# CAN_Tranceiver.net
KiCad netlist of a schematic drawn in Altium Designer
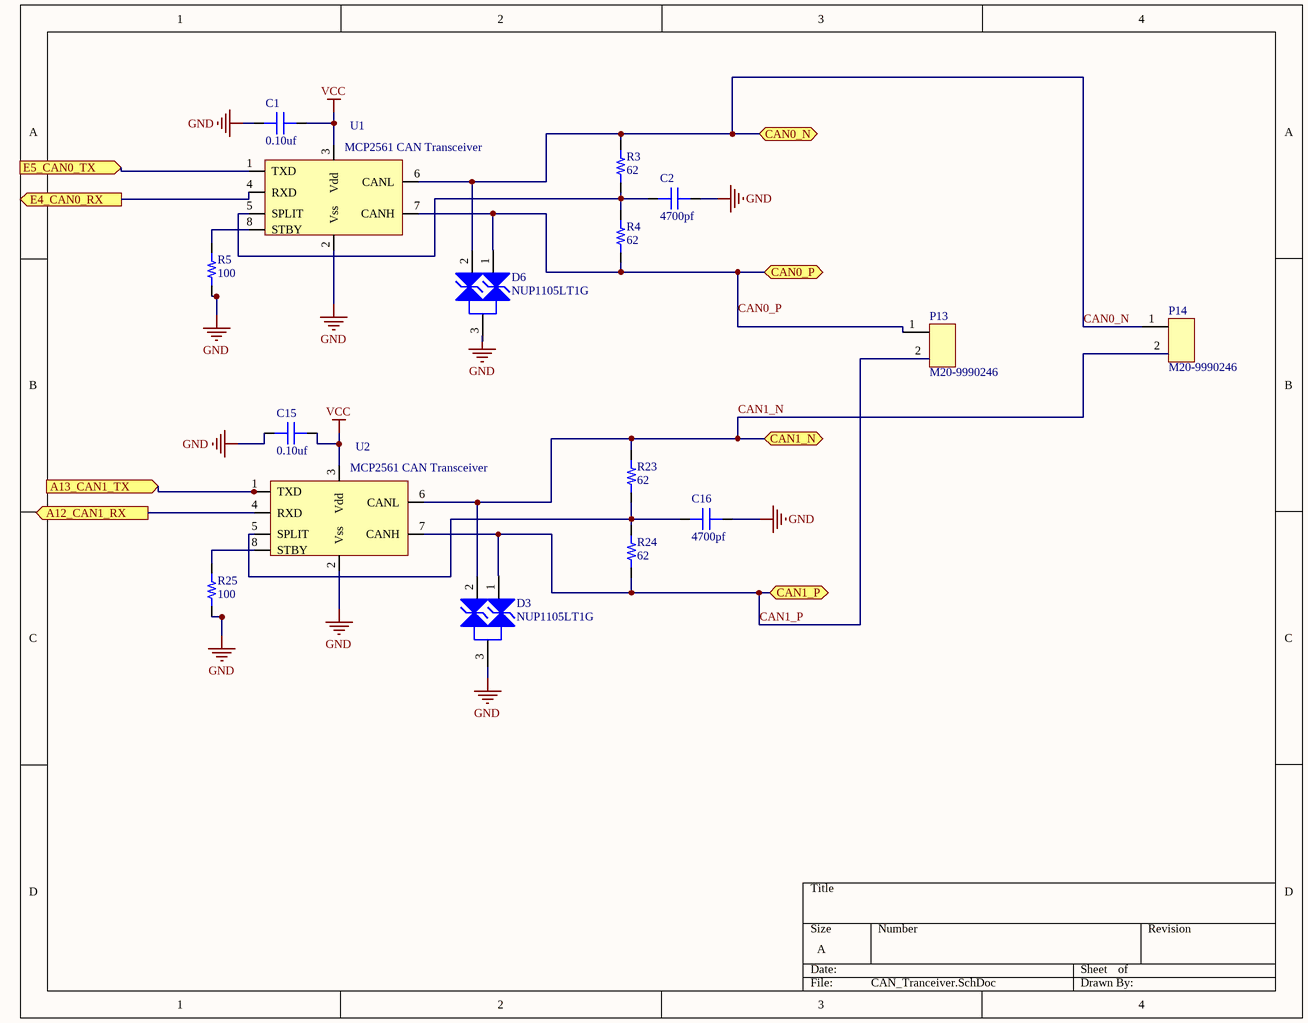
[diagram p0: CAN_Tranceiver.SchDoc]

(export (version "E")
  (design (tool "Eeschema 10.0.6"))
  (components
    (comp (ref "C1")
      (value "0.10uf")
      (footprint "CAP 0603/1608")
      (fields
        (field (name "Comment") "Capacitor MLCC 0.10uf 50V CAP 0603/1608")
        (field (name "CREATED_BY") "Nick Mah")
      )
      (libsource (lib "Altium-Lib") (part "Capacitor"))
    )
    (comp (ref "C2")
      (value "4700pf")
      (footprint "CAP 0603/1608")
      (fields
        (field (name "Comment") "Capacitor MLCC 4700pf 50V CAP 0603/1608")
        (field (name "CREATED_BY") "Nick Mah")
      )
      (libsource (lib "Altium-Lib") (part "Capacitor"))
    )
    (comp (ref "C15")
      (value "0.10uf")
      (footprint "CAP 0603/1608")
      (fields
        (field (name "Comment") "Capacitor MLCC 0.10uf 50V CAP 0603/1608")
        (field (name "CREATED_BY") "Nick Mah")
      )
      (libsource (lib "Altium-Lib") (part "Capacitor"))
    )
    (comp (ref "C16")
      (value "4700pf")
      (footprint "CAP 0603/1608")
      (fields
        (field (name "Comment") "Capacitor MLCC 4700pf 50V CAP 0603/1608")
        (field (name "CREATED_BY") "Nick Mah")
      )
      (libsource (lib "Altium-Lib") (part "Capacitor"))
    )
    (comp (ref "D3")
      (value "NUP1105LT1G")
      (footprint "SOT-23 (TO-236)")
      (description "ESD Protection Diode")
      (fields (field (name "POWER") "350W"))
      (libsource (lib "Altium-Lib") (part "NUP1105LT1G"))
    )
    (comp (ref "D6")
      (value "NUP1105LT1G")
      (footprint "SOT-23 (TO-236)")
      (description "ESD Protection Diode")
      (fields (field (name "POWER") "350W"))
      (libsource (lib "Altium-Lib") (part "NUP1105LT1G"))
    )
    (comp (ref "P13")
      (value "M20-9990246")
      (footprint "M20-9990246")
      (description "2 Pin VCC Power Header, Male")
      (fields (field (name "CREATED_BY") "Austin") (field (name "UPDATED_BY") "Null"))
      (libsource (lib "Altium-Lib") (part "M20-9990246"))
    )
    (comp (ref "P14")
      (value "M20-9990246")
      (footprint "M20-9990246")
      (description "2 Pin VCC Power Header, Male")
      (fields (field (name "CREATED_BY") "Austin") (field (name "UPDATED_BY") "Null"))
      (libsource (lib "Altium-Lib") (part "M20-9990246"))
    )
    (comp (ref "R3")
      (value "62")
      (footprint "RES 0603/1608")
      (fields
        (field (name "TOLERANCE") "5%")
        (field (name "POWER") "1/10W")
        (field (name "Comment") "Resistor 62 0603 1/10W 5%")
        (field (name "CREATED_BY") "Nick Mah")
      )
      (libsource (lib "Altium-Lib") (part "Resistor"))
    )
    (comp (ref "R4")
      (value "62")
      (footprint "RES 0603/1608")
      (fields
        (field (name "TOLERANCE") "5%")
        (field (name "POWER") "1/10W")
        (field (name "Comment") "Resistor 62 0603 1/10W 5%")
        (field (name "CREATED_BY") "Nick Mah")
      )
      (libsource (lib "Altium-Lib") (part "Resistor"))
    )
    (comp (ref "R5")
      (value "100")
      (footprint "RES 0603/1608")
      (fields
        (field (name "TOLERANCE") "10%")
        (field (name "POWER") "1/10W")
        (field (name "Comment") "Resistor 100 0603 1/10W 10%")
        (field (name "CREATED_BY") "Nick Mah")
      )
      (libsource (lib "Altium-Lib") (part "Resistor"))
    )
    (comp (ref "R23")
      (value "62")
      (footprint "RES 0603/1608")
      (fields
        (field (name "TOLERANCE") "5%")
        (field (name "POWER") "1/10W")
        (field (name "Comment") "Resistor 62 0603 1/10W 5%")
        (field (name "CREATED_BY") "Nick Mah")
      )
      (libsource (lib "Altium-Lib") (part "Resistor"))
    )
    (comp (ref "R24")
      (value "62")
      (footprint "RES 0603/1608")
      (fields
        (field (name "TOLERANCE") "5%")
        (field (name "POWER") "1/10W")
        (field (name "Comment") "Resistor 62 0603 1/10W 5%")
        (field (name "CREATED_BY") "Nick Mah")
      )
      (libsource (lib "Altium-Lib") (part "Resistor"))
    )
    (comp (ref "R25")
      (value "100")
      (footprint "RES 0603/1608")
      (fields
        (field (name "TOLERANCE") "10%")
        (field (name "POWER") "1/10W")
        (field (name "Comment") "Resistor 100 0603 1/10W 10%")
        (field (name "CREATED_BY") "Nick Mah")
      )
      (libsource (lib "Altium-Lib") (part "Resistor"))
    )
    (comp (ref "U1")
      (value "MCP2561 CAN Transceiver")
      (footprint "SOIC-8")
      (fields (field (name "MFRPARTNO") "MCP2561") (field (name "CREATED_BY") "Angel Delgado"))
      (libsource (lib "Altium-Lib") (part "MCP2561 CAN Transceiver"))
    )
    (comp (ref "U2")
      (value "MCP2561 CAN Transceiver")
      (footprint "SOIC-8")
      (fields (field (name "MFRPARTNO") "MCP2561") (field (name "CREATED_BY") "Angel Delgado"))
      (libsource (lib "Altium-Lib") (part "MCP2561 CAN Transceiver"))
    )
  )
  (nets
    (net (code "1") (name "/A12_CAN1_RX") (class "Default")
      (node (ref "U2") (pin "4") (pinfunction "RXD_4") (pintype "passive"))
    )
    (net (code "2") (name "/A13_CAN1_TX") (class "Default")
      (node (ref "U2") (pin "1") (pinfunction "TXD_1") (pintype "passive"))
    )
    (net (code "3") (name "/CAN0_N") (class "Default")
      (node (ref "D6") (pin "2") (pinfunction "K_2") (pintype "passive"))
      (node (ref "P14") (pin "1") (pinfunction "1_1") (pintype "passive"))
      (node (ref "R3") (pin "1") (pinfunction "1_1") (pintype "passive"))
      (node (ref "U1") (pin "6") (pinfunction "CANL_6") (pintype "passive"))
    )
    (net (code "4") (name "/CAN0_P") (class "Default")
      (node (ref "D6") (pin "1") (pinfunction "K_1") (pintype "passive"))
      (node (ref "P13") (pin "1") (pinfunction "1_1") (pintype "passive"))
      (node (ref "R4") (pin "2") (pinfunction "2_2") (pintype "passive"))
      (node (ref "U1") (pin "7") (pinfunction "CANH_7") (pintype "passive"))
    )
    (net (code "5") (name "/CAN1_N") (class "Default")
      (node (ref "D3") (pin "2") (pinfunction "K_2") (pintype "passive"))
      (node (ref "P14") (pin "2") (pinfunction "2_2") (pintype "passive"))
      (node (ref "R23") (pin "1") (pinfunction "1_1") (pintype "passive"))
      (node (ref "U2") (pin "6") (pinfunction "CANL_6") (pintype "passive"))
    )
    (net (code "6") (name "/CAN1_P") (class "Default")
      (node (ref "D3") (pin "1") (pinfunction "K_1") (pintype "passive"))
      (node (ref "P13") (pin "2") (pinfunction "2_2") (pintype "passive"))
      (node (ref "R24") (pin "2") (pinfunction "2_2") (pintype "passive"))
      (node (ref "U2") (pin "7") (pinfunction "CANH_7") (pintype "passive"))
    )
    (net (code "7") (name "/E4_CAN0_RX") (class "Default")
      (node (ref "U1") (pin "4") (pinfunction "RXD_4") (pintype "passive"))
    )
    (net (code "8") (name "/E5_CAN0_TX") (class "Default")
      (node (ref "U1") (pin "1") (pinfunction "TXD_1") (pintype "passive"))
    )
    (net (code "9") (name "GND") (class "Default")
      (node (ref "C1") (pin "1") (pinfunction "1_1") (pintype "passive"))
      (node (ref "C15") (pin "1") (pinfunction "1_1") (pintype "passive"))
      (node (ref "C16") (pin "1") (pinfunction "1_1") (pintype "passive"))
      (node (ref "C2") (pin "1") (pinfunction "1_1") (pintype "passive"))
      (node (ref "D3") (pin "3") (pinfunction "K_3") (pintype "passive"))
      (node (ref "D6") (pin "3") (pinfunction "K_3") (pintype "passive"))
      (node (ref "R25") (pin "1") (pinfunction "1_1") (pintype "passive"))
      (node (ref "R5") (pin "1") (pinfunction "1_1") (pintype "passive"))
      (node (ref "U1") (pin "2") (pinfunction "Vss_2") (pintype "passive"))
      (node (ref "U2") (pin "2") (pinfunction "Vss_2") (pintype "passive"))
    )
    (net (code "10") (name "Net-(U1-SPLIT)") (class "Default")
      (node (ref "C2") (pin "2") (pinfunction "2_2") (pintype "passive"))
      (node (ref "R3") (pin "2") (pinfunction "2_2") (pintype "passive"))
      (node (ref "R4") (pin "1") (pinfunction "1_1") (pintype "passive"))
      (node (ref "U1") (pin "5") (pinfunction "SPLIT_5") (pintype "passive"))
    )
    (net (code "11") (name "Net-(U1-STBY)") (class "Default")
      (node (ref "R5") (pin "2") (pinfunction "2_2") (pintype "passive"))
      (node (ref "U1") (pin "8") (pinfunction "STBY_8") (pintype "passive"))
    )
    (net (code "12") (name "Net-(U2-SPLIT)") (class "Default")
      (node (ref "C16") (pin "2") (pinfunction "2_2") (pintype "passive"))
      (node (ref "R23") (pin "2") (pinfunction "2_2") (pintype "passive"))
      (node (ref "R24") (pin "1") (pinfunction "1_1") (pintype "passive"))
      (node (ref "U2") (pin "5") (pinfunction "SPLIT_5") (pintype "passive"))
    )
    (net (code "13") (name "Net-(U2-STBY)") (class "Default")
      (node (ref "R25") (pin "2") (pinfunction "2_2") (pintype "passive"))
      (node (ref "U2") (pin "8") (pinfunction "STBY_8") (pintype "passive"))
    )
    (net (code "14") (name "VCC") (class "Default")
      (node (ref "C1") (pin "2") (pinfunction "2_2") (pintype "passive"))
      (node (ref "C15") (pin "2") (pinfunction "2_2") (pintype "passive"))
      (node (ref "U1") (pin "3") (pinfunction "Vdd_3") (pintype "passive"))
      (node (ref "U2") (pin "3") (pinfunction "Vdd_3") (pintype "passive"))
    )
  )
)
